# Haar_Primal_HardMount.net
KiCad netlist of a schematic drawn in EAGLE
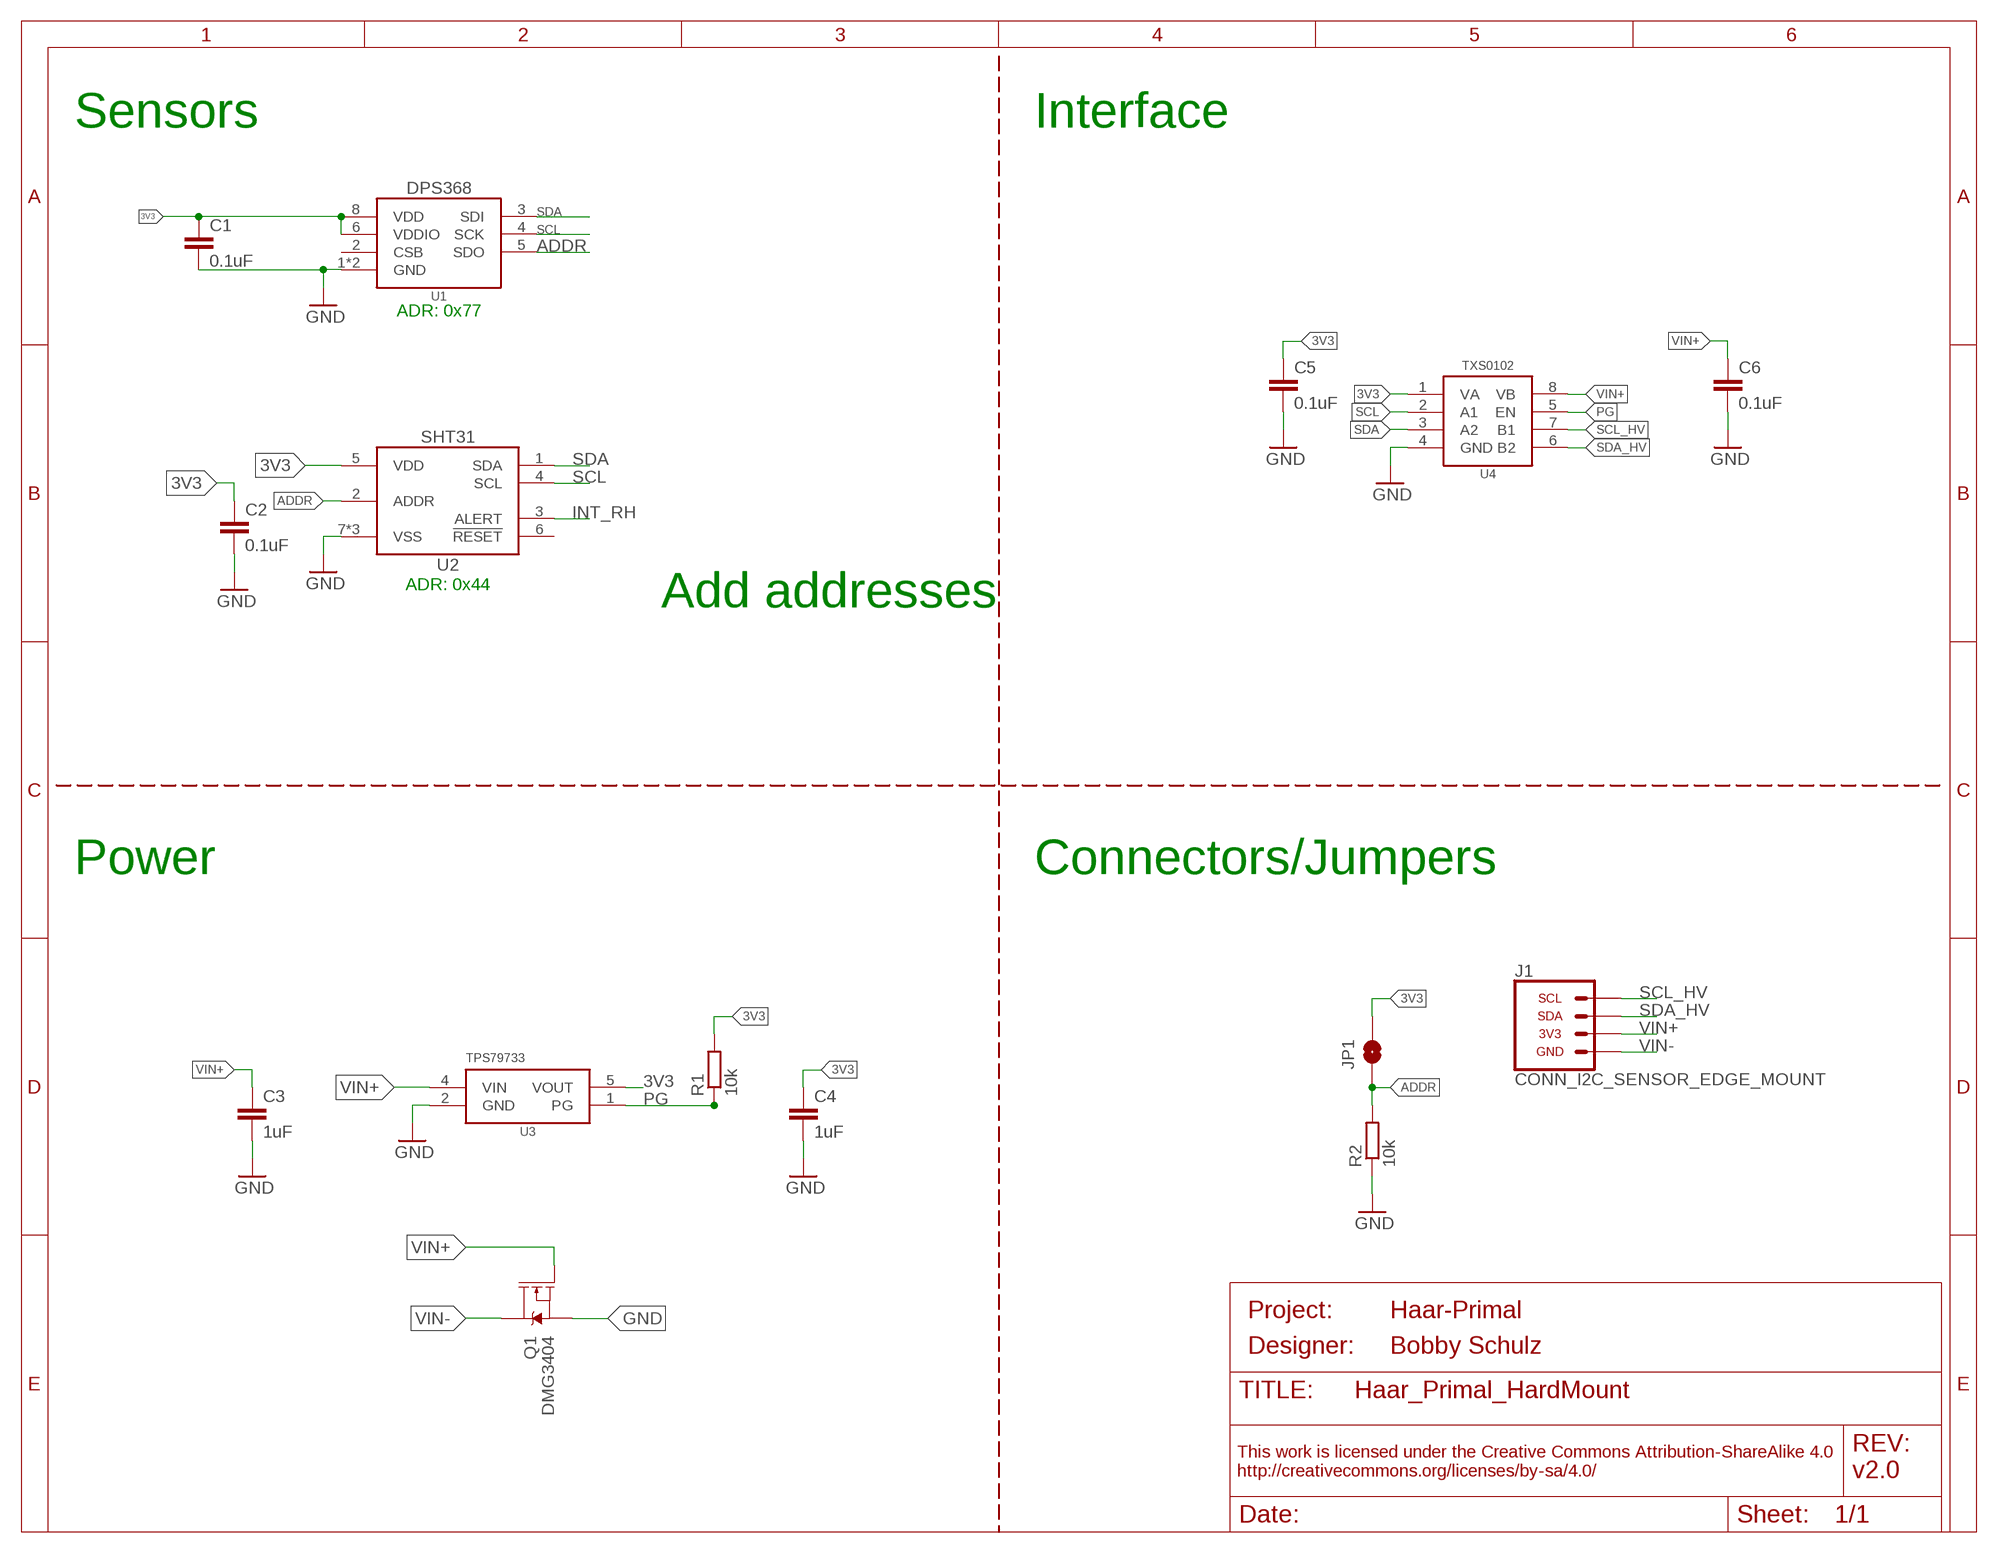
[diagram p0: schematic, sheet 1]

(export (version "E")
  (design (tool "Eeschema 10.0.6"))
  (components
    (comp (ref "C1")
      (value "0.1uF")
      (footprint "eagle-import:C0603")
      (fields (field (name "MF") "Murata") (field (name "MPN") "GCM188R71E104KA57D"))
      (libsource (lib "eagle-import") (part "C-EUC06030.1UF"))
    )
    (comp (ref "C2")
      (value "0.1uF")
      (footprint "eagle-import:C0603")
      (fields (field (name "MF") "Murata") (field (name "MPN") "GCM188R71E104KA57D"))
      (libsource (lib "eagle-import") (part "C-EUC06030.1UF"))
    )
    (comp (ref "C3")
      (value "1uF")
      (footprint "eagle-import:C0603")
      (fields (field (name "MF") "Yaiyo Yuden") (field (name "MPN") "EMK107BJ105KA-T"))
      (libsource (lib "eagle-import") (part "C-EUC06031UF"))
    )
    (comp (ref "C4")
      (value "1uF")
      (footprint "eagle-import:C0603")
      (fields (field (name "MF") "Yaiyo Yuden") (field (name "MPN") "EMK107BJ105KA-T"))
      (libsource (lib "eagle-import") (part "C-EUC06031UF"))
    )
    (comp (ref "C5")
      (value "0.1uF")
      (footprint "eagle-import:C0603")
      (fields (field (name "MF") "Murata") (field (name "MPN") "GCM188R71E104KA57D"))
      (libsource (lib "eagle-import") (part "C-EUC06030.1UF"))
    )
    (comp (ref "C6")
      (value "0.1uF")
      (footprint "eagle-import:C0603")
      (fields (field (name "MF") "Murata") (field (name "MPN") "GCM188R71E104KA57D"))
      (libsource (lib "eagle-import") (part "C-EUC06030.1UF"))
    )
    (comp (ref "J1")
      (value "CONN_I2C_SENSOR_EDGE_MOUNT")
      (footprint "eagle-import:SOLDERCUP_CONN_QUAD")
      (fields (field (name "MF") "TE Connectivity") (field (name "MPN") "1838893-2"))
      (libsource (lib "eagle-import") (part "CONN_I2C_SENSOR_EDGE_MOUNT"))
    )
    (comp (ref "JP1")
      (value "JUMPER-SMT_2_NO_SILK")
      (footprint "eagle-import:SMT-JUMPER_2_NO_SILK")
      (libsource (lib "eagle-import") (part "JUMPER-SMT_2_NO_SILK"))
    )
    (comp (ref "Q1")
      (value "DMG3404")
      (footprint "eagle-import:SOT23-3")
      (fields (field (name "MF") "Diodes Incorporated") (field (name "MPN") "DMG3404L-7"))
      (libsource (lib "eagle-import") (part "MOSFET-NCH-DMG3404L"))
    )
    (comp (ref "R1")
      (value "10k")
      (footprint "eagle-import:R0603")
      (fields
        (field (name "MF") "Yageo")
        (field (name "MPN") "RC0603FR-07100KL")
        (field (name "VALUE_PART") "100k")
      )
      (libsource (lib "eagle-import") (part "R-EU_R0603100K"))
    )
    (comp (ref "R2")
      (value "10k")
      (footprint "eagle-import:R0603")
      (fields
        (field (name "MF") "Yageo")
        (field (name "MPN") "RC0603FR-07100KL")
        (field (name "VALUE_PART") "100k")
      )
      (libsource (lib "eagle-import") (part "R-EU_R0603100K"))
    )
    (comp (ref "U1")
      (value "DPS368")
      (footprint "eagle-import:PG-VLGA-8")
      (fields
        (field (name "DISP") "DPS368")
        (field (name "MF") "Infineon")
        (field (name "MPN") "DPS368XTSA1")
      )
      (libsource (lib "eagle-import") (part "DPS368"))
    )
    (comp (ref "U2")
      (value "SHT31DFN")
      (footprint "eagle-import:DFN_8_2.5X2.5")
      (fields
        (field (name "DISP") "SHT31")
        (field (name "MF") "Sensirion")
        (field (name "MPN") "SHT31-DIS-F2.5KS")
      )
      (libsource (lib "eagle-import") (part "SHT3DFN1"))
    )
    (comp (ref "U3")
      (value "TPS79733")
      (footprint "eagle-import:DCK_R-PDSO-G5")
      (fields (field (name "DISP") "TPS79733") (field (name "MF") "TI") (field (name "MPN") "TPS79733DCKR"))
      (libsource (lib "eagle-import") (part "TPS79733"))
    )
    (comp (ref "U4")
      (value "TXS0102DQM")
      (footprint "eagle-import:DQM_R-PX2SON-N8")
      (fields (field (name "MF") "TI") (field (name "MPN") "TXS0102DQMR"))
      (libsource (lib "eagle-import") (part "TXS0102DQM"))
    )
  )
  (nets
    (net (code "1") (name "/INT_RH") (class "Default")
      (node (ref "U2") (pin "3") (pinfunction "ALERT_3") (pintype "output"))
    )
    (net (code "2") (name "3V3") (class "Default")
      (node (ref "C1") (pin "1") (pinfunction "1_1") (pintype "passive"))
      (node (ref "C2") (pin "1") (pinfunction "1_1") (pintype "passive"))
      (node (ref "C4") (pin "1") (pinfunction "1_1") (pintype "passive"))
      (node (ref "C5") (pin "1") (pinfunction "1_1") (pintype "passive"))
      (node (ref "JP1") (pin "2") (pinfunction "2_2") (pintype "passive"))
      (node (ref "R1") (pin "2") (pinfunction "2_2") (pintype "passive"))
      (node (ref "U1") (pin "6") (pinfunction "VDDIO_6") (pintype "bidirectional"))
      (node (ref "U1") (pin "8") (pinfunction "VDD_8") (pintype "power_in"))
      (node (ref "U2") (pin "5") (pinfunction "VDD_5") (pintype "power_in"))
      (node (ref "U3") (pin "5") (pinfunction "VOUT_5") (pintype "bidirectional"))
      (node (ref "U4") (pin "1") (pinfunction "VA_1") (pintype "power_in"))
    )
    (net (code "3") (name "ADDR") (class "Default")
      (node (ref "JP1") (pin "1") (pinfunction "1_1") (pintype "passive"))
      (node (ref "R2") (pin "2") (pinfunction "2_2") (pintype "passive"))
      (node (ref "U1") (pin "5") (pinfunction "SDO_5") (pintype "bidirectional"))
      (node (ref "U2") (pin "2") (pinfunction "ADDR_2") (pintype "input"))
    )
    (net (code "4") (name "GND") (class "Default")
      (node (ref "C1") (pin "2") (pinfunction "2_2") (pintype "passive"))
      (node (ref "C2") (pin "2") (pinfunction "2_2") (pintype "passive"))
      (node (ref "C3") (pin "2") (pinfunction "2_2") (pintype "passive"))
      (node (ref "C4") (pin "2") (pinfunction "2_2") (pintype "passive"))
      (node (ref "C5") (pin "2") (pinfunction "2_2") (pintype "passive"))
      (node (ref "C6") (pin "2") (pinfunction "2_2") (pintype "passive"))
      (node (ref "Q1") (pin "2") (pinfunction "S_2") (pintype "bidirectional"))
      (node (ref "R2") (pin "1") (pinfunction "1_1") (pintype "passive"))
      (node (ref "U1") (pin "1") (pinfunction "GND_1") (pintype "power_in"))
      (node (ref "U1") (pin "7") (pinfunction "GND_7") (pintype "power_in"))
      (node (ref "U2") (pin "7") (pinfunction "VSS_7") (pintype "power_in"))
      (node (ref "U2") (pin "8") (pinfunction "VSS_8") (pintype "power_in"))
      (node (ref "U2") (pin "EP") (pinfunction "VSS_EP") (pintype "power_in"))
      (node (ref "U3") (pin "2") (pinfunction "GND_2") (pintype "bidirectional"))
      (node (ref "U4") (pin "4") (pinfunction "GND_4") (pintype "power_in"))
    )
    (net (code "5") (name "PG") (class "Default")
      (node (ref "R1") (pin "1") (pinfunction "1_1") (pintype "passive"))
      (node (ref "U3") (pin "1") (pinfunction "PG_1") (pintype "bidirectional"))
      (node (ref "U4") (pin "5") (pinfunction "EN_5") (pintype "input"))
    )
    (net (code "6") (name "SCL") (class "Default")
      (node (ref "U1") (pin "4") (pinfunction "SCK_4") (pintype "bidirectional"))
      (node (ref "U2") (pin "4") (pinfunction "SCL_4") (pintype "input"))
      (node (ref "U4") (pin "2") (pinfunction "A1_2") (pintype "bidirectional"))
    )
    (net (code "7") (name "SCL_HV") (class "Default")
      (node (ref "J1") (pin "3") (pinfunction "SCL_3") (pintype "passive"))
      (node (ref "U4") (pin "7") (pinfunction "B1_7") (pintype "bidirectional"))
    )
    (net (code "8") (name "SDA") (class "Default")
      (node (ref "U1") (pin "3") (pinfunction "SDI_3") (pintype "bidirectional"))
      (node (ref "U2") (pin "1") (pinfunction "SDA_1") (pintype "bidirectional"))
      (node (ref "U4") (pin "3") (pinfunction "A2_3") (pintype "bidirectional"))
    )
    (net (code "9") (name "SDA_HV") (class "Default")
      (node (ref "J1") (pin "1") (pinfunction "SDA_1") (pintype "passive"))
      (node (ref "U4") (pin "6") (pinfunction "B2_6") (pintype "bidirectional"))
    )
    (net (code "10") (name "VIN+") (class "Default")
      (node (ref "C3") (pin "1") (pinfunction "1_1") (pintype "passive"))
      (node (ref "C6") (pin "1") (pinfunction "1_1") (pintype "passive"))
      (node (ref "J1") (pin "2") (pinfunction "3V3_2") (pintype "passive"))
      (node (ref "Q1") (pin "1") (pinfunction "G_1") (pintype "bidirectional"))
      (node (ref "U3") (pin "4") (pinfunction "VIN_4") (pintype "bidirectional"))
      (node (ref "U4") (pin "8") (pinfunction "VB_8") (pintype "power_in"))
    )
    (net (code "11") (name "VIN-") (class "Default")
      (node (ref "J1") (pin "4") (pinfunction "GND_4") (pintype "passive"))
      (node (ref "Q1") (pin "3") (pinfunction "D_3") (pintype "bidirectional"))
    )
    (net (code "12") (name "unconnected-(U1-CSB-Pad2)") (class "Default")
      (node (ref "U1") (pin "2") (pinfunction "CSB_2") (pintype "bidirectional"))
    )
    (net (code "13") (name "unconnected-(U2-~{RESET}-Pad6)") (class "Default")
      (node (ref "U2") (pin "6") (pinfunction "~{RESET}_6") (pintype "input"))
    )
  )
)
